# 5V_to_3V3.net
KiCad netlist of a schematic drawn in Altium Designer
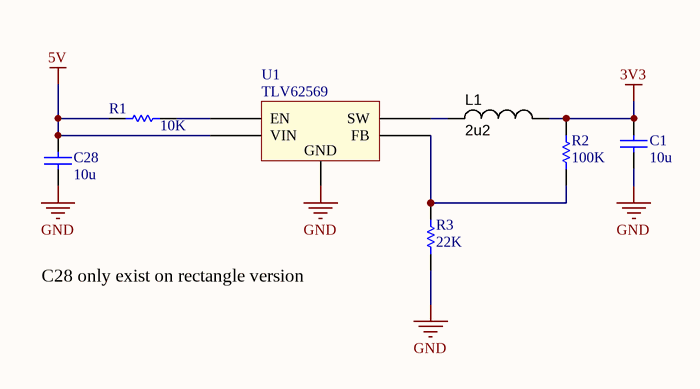
[diagram p0: 5V_to_3V3.SchDoc]

(export (version "E")
  (design (tool "Eeschema 10.0.6"))
  (components
    (comp (ref "C1")
      (value "10u")
      (footprint "CAPC2012X135N")
      (description "Capacitor")
      (fields (field (name "Comment") "Cap") (field (name "PUBLISHER") "Altium Limited"))
      (libsource (lib "IOBoard_Low") (part "Cap"))
    )
    (comp (ref "C28")
      (value "10u")
      (footprint "CAPC2012X135N")
      (description "Capacitor")
      (fields (field (name "Comment") "Cap") (field (name "PUBLISHER") "Altium Limited"))
      (libsource (lib "IOBoard_Low") (part "Cap"))
    )
    (comp (ref "L1")
      (value "2u2")
      (footprint "INDM3225X240N")
      (description "IHLP SMD 4040")
      (fields (field (name "Comment") "inductor"))
      (libsource (lib "IOBoard_Low") (part "INDC"))
    )
    (comp (ref "R1")
      (value "10K")
      (footprint "RESC1608X55N")
      (description "Resistor")
      (fields (field (name "Comment") "Res1") (field (name "PUBLISHER") "Altium Limited"))
      (libsource (lib "IOBoard_Low") (part "Res1"))
    )
    (comp (ref "R2")
      (value "100K")
      (footprint "RESC2012X70N")
      (description "Resistor")
      (fields (field (name "Comment") "Res1") (field (name "PUBLISHER") "Altium Limited"))
      (libsource (lib "IOBoard_Low") (part "Res1"))
    )
    (comp (ref "R3")
      (value "22K")
      (footprint "RESC2012X70N")
      (description "Resistor")
      (fields (field (name "Comment") "Res1") (field (name "PUBLISHER") "Altium Limited"))
      (libsource (lib "IOBoard_Low") (part "Res1"))
    )
    (comp (ref "U1")
      (value "TLV62569")
      (footprint "SOT23-5")
      (description "2-A High Efficiency Synchronous Buck Converter in SOT Package")
      (fields (field (name "MANUFACTURER") "TI"))
      (libsource (lib "IOBoard") (part "TLV62569"))
    )
  )
  (nets
    (net (code "1") (name "3V3") (class "Default")
      (node (ref "C1") (pin "2") (pinfunction "2_2") (pintype "passive"))
      (node (ref "L1") (pin "2") (pinfunction "2_2") (pintype "passive"))
      (node (ref "R2") (pin "2") (pinfunction "2_2") (pintype "passive"))
    )
    (net (code "2") (name "5V") (class "Default")
      (node (ref "C28") (pin "2") (pinfunction "2_2") (pintype "passive"))
      (node (ref "R1") (pin "1") (pinfunction "1_1") (pintype "passive"))
      (node (ref "U1") (pin "4") (pinfunction "VIN_4") (pintype "passive"))
    )
    (net (code "3") (name "GND") (class "Default")
      (node (ref "C1") (pin "1") (pinfunction "1_1") (pintype "passive"))
      (node (ref "C28") (pin "1") (pinfunction "1_1") (pintype "passive"))
      (node (ref "R3") (pin "2") (pinfunction "2_2") (pintype "passive"))
      (node (ref "U1") (pin "2") (pinfunction "GND_2") (pintype "passive"))
    )
    (net (code "4") (name "Net-(U1-EN)") (class "Default")
      (node (ref "R1") (pin "2") (pinfunction "2_2") (pintype "passive"))
      (node (ref "U1") (pin "1") (pinfunction "EN_1") (pintype "passive"))
    )
    (net (code "5") (name "Net-(U1-FB)") (class "Default")
      (node (ref "R2") (pin "1") (pinfunction "1_1") (pintype "passive"))
      (node (ref "R3") (pin "1") (pinfunction "1_1") (pintype "passive"))
      (node (ref "U1") (pin "5") (pinfunction "FB_5") (pintype "passive"))
    )
    (net (code "6") (name "Net-(U1-SW)") (class "Default")
      (node (ref "L1") (pin "1") (pinfunction "1_1") (pintype "passive"))
      (node (ref "U1") (pin "3") (pinfunction "SW_3") (pintype "passive"))
    )
  )
)
